# Power.net
KiCad netlist of a schematic drawn in Altium Designer
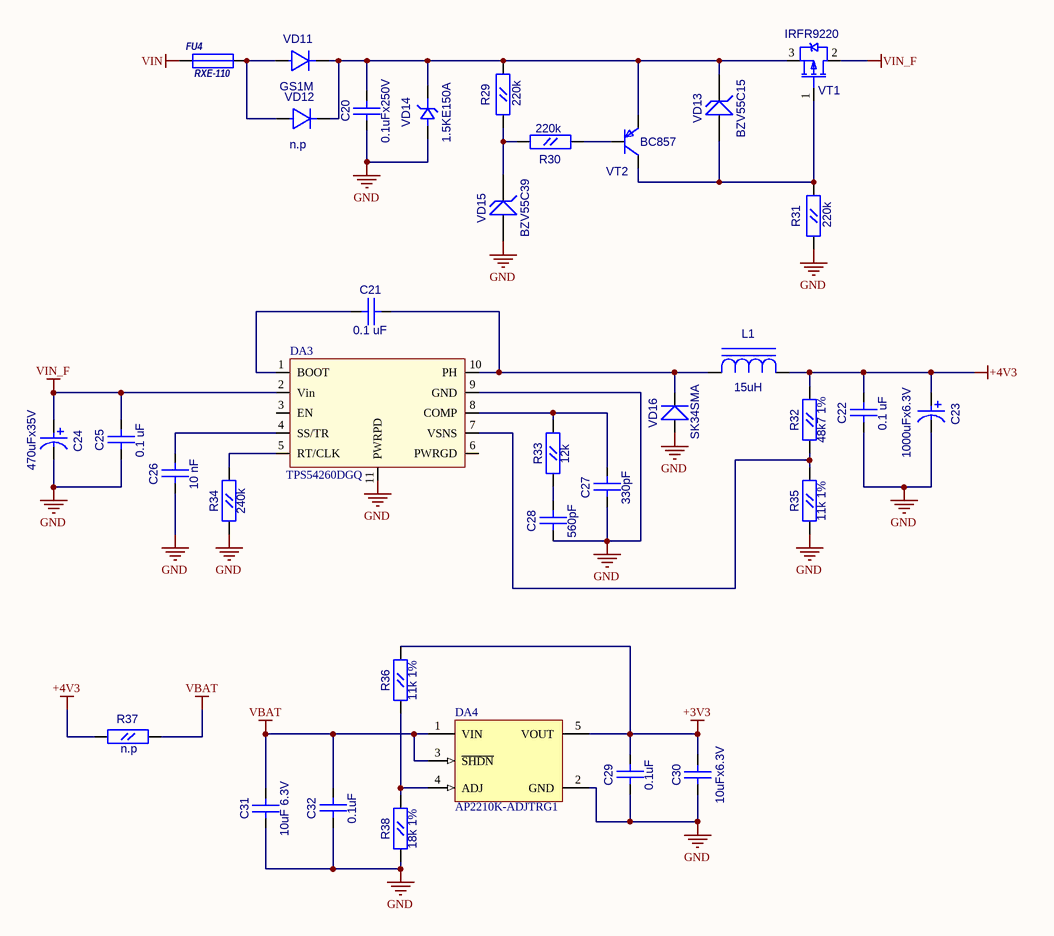
[diagram p0: Power.SchDoc]

(export (version "E")
  (design (tool "Eeschema 10.0.6"))
  (components
    (comp (ref "C20")
      (value "0.1uFx250V")
      (footprint "CC1206")
      (description "CC1206")
      (libsource (lib "gprs_modem_2") (part "CC1206"))
    )
    (comp (ref "C21")
      (value "0.1 uF")
      (footprint "CC0603")
      (description "CC0603")
      (libsource (lib "gprs_modem_2") (part "CC0603"))
    )
    (comp (ref "C22")
      (value "0.1 uF")
      (footprint "CC0603")
      (description "CC0603")
      (libsource (lib "gprs_modem_2") (part "CC0603"))
    )
    (comp (ref "C23")
      (value "1000uFx6.3V")
      (footprint "CC8X3.5")
      (description "CAP0.35")
      (libsource (lib "gprs_modem_2") (part "CAP0.35"))
    )
    (comp (ref "C24")
      (value "470uFx35V")
      (footprint "CC16X10_CAP0.5(1)(Primary)")
      (description "CAP0.5(1)")
      (libsource (lib "gprs_modem_2") (part "CAP0.5(1)"))
    )
    (comp (ref "C25")
      (value "0.1 uF")
      (footprint "CC0603")
      (description "CC0603")
      (libsource (lib "gprs_modem_2") (part "CC0603"))
    )
    (comp (ref "C26")
      (value "10 nF")
      (footprint "CC0603")
      (description "CC0603")
      (libsource (lib "gprs_modem_2") (part "CC0603"))
    )
    (comp (ref "C27")
      (value "330pF")
      (footprint "CC0603")
      (description "CC0603")
      (libsource (lib "gprs_modem_2") (part "CC0603"))
    )
    (comp (ref "C28")
      (value "560pF")
      (footprint "CC0603")
      (description "CC0603")
      (libsource (lib "gprs_modem_2") (part "CC0603"))
    )
    (comp (ref "C29")
      (value "0.1uF")
      (footprint "CC0603")
      (description "CC0603")
      (libsource (lib "gprs_modem_2") (part "CC0603"))
    )
    (comp (ref "C30")
      (value "10uFx6.3V")
      (footprint "CC0805")
      (description "CC0805")
      (libsource (lib "gprs_modem_2") (part "CC0805"))
    )
    (comp (ref "C31")
      (value "10uF 6.3V")
      (footprint "CC0805")
      (description "CC0805")
      (libsource (lib "gprs_modem_2") (part "CC0805"))
    )
    (comp (ref "C32")
      (value "0.1uF")
      (footprint "CC0603")
      (description "CC0603")
      (libsource (lib "gprs_modem_2") (part "CC0603"))
    )
    (comp (ref "DA3")
      (value "TPS54260DGQ")
      (footprint "S-PDSO-G10")
      (libsource (lib "gprs_modem_2") (part "TPS54260DGQ"))
    )
    (comp (ref "DA4")
      (value "AP2210K-ADJTRG1")
      (footprint "SOT23-5")
      (fields (field (name "PUBLISHER") "Altium Limited"))
      (libsource (lib "gprs_modem_2") (part "MCP1824T-ADJE/OT"))
    )
    (comp (ref "FU4")
      (value "RXE-110")
      (footprint "RXE-110")
      (libsource (lib "gprs_modem_2") (part "RXE-110"))
    )
    (comp (ref "L1")
      (value "15uH")
      (footprint "SDR0805")
      (description "SDR0805")
      (libsource (lib "gprs_modem_2") (part "SDR0805"))
    )
    (comp (ref "R29")
      (value "220k")
      (footprint "RC0603")
      (description "RC0603")
      (libsource (lib "gprs_modem_2") (part "RC0603"))
    )
    (comp (ref "R30")
      (value "220k")
      (footprint "RC0603")
      (description "RC0603")
      (libsource (lib "gprs_modem_2") (part "RC0603"))
    )
    (comp (ref "R31")
      (value "220k")
      (footprint "RC0603")
      (description "RC0603")
      (libsource (lib "gprs_modem_2") (part "RC0603"))
    )
    (comp (ref "R32")
      (value "48k7 1%")
      (footprint "RC0603")
      (description "RC0603")
      (libsource (lib "gprs_modem_2") (part "RC0603"))
    )
    (comp (ref "R33")
      (value "12k")
      (footprint "RC0603")
      (description "RC0603")
      (libsource (lib "gprs_modem_2") (part "RC0603"))
    )
    (comp (ref "R34")
      (value "240k")
      (footprint "RC0603")
      (description "RC0603")
      (libsource (lib "gprs_modem_2") (part "RC0603"))
    )
    (comp (ref "R35")
      (value "11k 1%")
      (footprint "RC0603")
      (description "RC0603")
      (libsource (lib "gprs_modem_2") (part "RC0603"))
    )
    (comp (ref "R36")
      (value "11k 1%")
      (footprint "RC0603")
      (description "RC0603")
      (libsource (lib "gprs_modem_2") (part "RC0603"))
    )
    (comp (ref "R37")
      (value "n.p")
      (footprint "RC0805")
      (description "RC0805")
      (libsource (lib "gprs_modem_2") (part "RC0805"))
    )
    (comp (ref "R38")
      (value "18k 1%")
      (footprint "RC0603")
      (description "RC0603")
      (libsource (lib "gprs_modem_2") (part "RC0603"))
    )
    (comp (ref "VD11") (value "GS1M") (footprint "SMA") (libsource (lib "gprs_modem_2") (part "GS1M")))
    (comp (ref "VD12")
      (value "n.p")
      (footprint "SMA")
      (description "GS1M")
      (libsource (lib "gprs_modem_2") (part "GS1M"))
    )
    (comp (ref "VD13")
      (value "BZV55C15")
      (footprint "SOD-80")
      (description "Zener Voltage Regulator Diode")
      (libsource (lib "gprs_modem_2") (part "BZV55C12"))
    )
    (comp (ref "VD14")
      (value "1.5KE150A")
      (footprint "DO-201")
      (description "1.5KE")
      (libsource (lib "gprs_modem_2") (part "1.5KE"))
    )
    (comp (ref "VD15")
      (value "BZV55C39")
      (footprint "SOD-80")
      (description "Zener Voltage Regulator Diode")
      (libsource (lib "gprs_modem_2") (part "BZV55C12"))
    )
    (comp (ref "VD16")
      (value "SK34SMA")
      (footprint "SMA")
      (description "Schottky Rectifier")
      (libsource (lib "gprs_modem") (part "SK34SMA"))
    )
    (comp (ref "VT1")
      (value "IRFR9220")
      (footprint "D-PAK(TO-252AA)")
      (description "HEXFET Power MOSFET")
      (libsource (lib "gprs_modem_2") (part "IRFR9220"))
    )
    (comp (ref "VT2")
      (value "BC857")
      (footprint "SOT-23(123)")
      (description "PNP 100ma transistor")
      (libsource (lib "gprs_modem_2") (part "BC857B"))
    )
  )
  (nets
    (net (code "1") (name "+3V3") (class "Default")
      (node (ref "C29") (pin "1") (pinfunction "A_1") (pintype "passive"))
      (node (ref "C30") (pin "2") (pinfunction "B_2") (pintype "passive"))
      (node (ref "DA4") (pin "5") (pinfunction "VOUT_5") (pintype "power_in"))
      (node (ref "R36") (pin "2") (pinfunction "B_2") (pintype "passive"))
    )
    (net (code "2") (name "+4V3") (class "Default")
      (node (ref "C22") (pin "1") (pinfunction "A_1") (pintype "passive"))
      (node (ref "C23") (pin "1") (pintype "passive"))
      (node (ref "L1") (pin "2") (pinfunction "A_2") (pintype "passive"))
      (node (ref "R32") (pin "2") (pinfunction "B_2") (pintype "passive"))
      (node (ref "R37") (pin "1") (pinfunction "A_1") (pintype "passive"))
    )
    (net (code "3") (name "GND") (class "Default")
      (node (ref "C20") (pin "1") (pinfunction "A_1") (pintype "passive"))
      (node (ref "C22") (pin "2") (pinfunction "B_2") (pintype "passive"))
      (node (ref "C23") (pin "2") (pintype "passive"))
      (node (ref "C24") (pin "1") (pintype "passive"))
      (node (ref "C25") (pin "2") (pinfunction "B_2") (pintype "passive"))
      (node (ref "C26") (pin "2") (pinfunction "B_2") (pintype "passive"))
      (node (ref "C27") (pin "2") (pinfunction "B_2") (pintype "passive"))
      (node (ref "C28") (pin "2") (pinfunction "B_2") (pintype "passive"))
      (node (ref "C29") (pin "2") (pinfunction "B_2") (pintype "passive"))
      (node (ref "C30") (pin "1") (pinfunction "A_1") (pintype "passive"))
      (node (ref "C31") (pin "1") (pinfunction "A_1") (pintype "passive"))
      (node (ref "C32") (pin "2") (pinfunction "B_2") (pintype "passive"))
      (node (ref "DA3") (pin "11") (pinfunction "PWRPD_11") (pintype "passive"))
      (node (ref "DA3") (pin "9") (pinfunction "GND_9") (pintype "passive"))
      (node (ref "DA4") (pin "2") (pinfunction "GND_2") (pintype "power_in"))
      (node (ref "R31") (pin "1") (pinfunction "A_1") (pintype "passive"))
      (node (ref "R34") (pin "1") (pinfunction "A_1") (pintype "passive"))
      (node (ref "R35") (pin "1") (pinfunction "A_1") (pintype "passive"))
      (node (ref "R38") (pin "1") (pinfunction "A_1") (pintype "passive"))
      (node (ref "VD14") (pin "1") (pinfunction "A_1") (pintype "passive"))
      (node (ref "VD15") (pin "1") (pinfunction "A_1") (pintype "passive"))
      (node (ref "VD16") (pin "1") (pinfunction "A_1") (pintype "passive"))
    )
    (net (code "4") (name "Net-(C20-B)") (class "Default")
      (node (ref "C20") (pin "2") (pinfunction "B_2") (pintype "passive"))
      (node (ref "R29") (pin "2") (pinfunction "B_2") (pintype "passive"))
      (node (ref "VD11") (pin "2") (pinfunction "K_2") (pintype "passive"))
      (node (ref "VD12") (pin "2") (pinfunction "K_2") (pintype "passive"))
      (node (ref "VD13") (pin "2") (pintype "passive"))
      (node (ref "VD14") (pin "2") (pinfunction "K_2") (pintype "passive"))
      (node (ref "VT1") (pin "3") (pinfunction "S_3") (pintype "passive"))
      (node (ref "VT2") (pin "2") (pinfunction "E_2") (pintype "passive"))
    )
    (net (code "5") (name "Net-(C21-A)") (class "Default")
      (node (ref "C21") (pin "1") (pinfunction "A_1") (pintype "passive"))
      (node (ref "DA3") (pin "10") (pinfunction "PH_10") (pintype "passive"))
      (node (ref "L1") (pin "1") (pinfunction "C_1") (pintype "passive"))
      (node (ref "VD16") (pin "2") (pinfunction "K_2") (pintype "passive"))
    )
    (net (code "6") (name "Net-(C21-B)") (class "Default")
      (node (ref "C21") (pin "2") (pinfunction "B_2") (pintype "passive"))
      (node (ref "DA3") (pin "1") (pinfunction "BOOT_1") (pintype "passive"))
    )
    (net (code "7") (name "Net-(C26-A)") (class "Default")
      (node (ref "C26") (pin "1") (pinfunction "A_1") (pintype "passive"))
      (node (ref "DA3") (pin "4") (pinfunction "SS/TR_4") (pintype "passive"))
    )
    (net (code "8") (name "Net-(C27-A)") (class "Default")
      (node (ref "C27") (pin "1") (pinfunction "A_1") (pintype "passive"))
      (node (ref "DA3") (pin "8") (pinfunction "COMP_8") (pintype "passive"))
      (node (ref "R33") (pin "2") (pinfunction "B_2") (pintype "passive"))
    )
    (net (code "9") (name "Net-(C28-A)") (class "Default")
      (node (ref "C28") (pin "1") (pinfunction "A_1") (pintype "passive"))
      (node (ref "R33") (pin "1") (pinfunction "A_1") (pintype "passive"))
    )
    (net (code "10") (name "Net-(DA3-RT{slash}CLK)") (class "Default")
      (node (ref "DA3") (pin "5") (pinfunction "RT/CLK_5") (pintype "passive"))
      (node (ref "R34") (pin "2") (pinfunction "B_2") (pintype "passive"))
    )
    (net (code "11") (name "Net-(DA3-VSNS)") (class "Default")
      (node (ref "DA3") (pin "7") (pinfunction "VSNS_7") (pintype "passive"))
      (node (ref "R32") (pin "1") (pinfunction "A_1") (pintype "passive"))
      (node (ref "R35") (pin "2") (pinfunction "B_2") (pintype "passive"))
    )
    (net (code "12") (name "Net-(DA4-ADJ)") (class "Default")
      (node (ref "DA4") (pin "4") (pinfunction "ADJ_4") (pintype "input"))
      (node (ref "R36") (pin "1") (pinfunction "A_1") (pintype "passive"))
      (node (ref "R38") (pin "2") (pinfunction "B_2") (pintype "passive"))
    )
    (net (code "13") (name "Net-(R29-A)") (class "Default")
      (node (ref "R29") (pin "1") (pinfunction "A_1") (pintype "passive"))
      (node (ref "R30") (pin "2") (pinfunction "B_2") (pintype "passive"))
      (node (ref "VD15") (pin "2") (pintype "passive"))
    )
    (net (code "14") (name "Net-(R30-A)") (class "Default")
      (node (ref "R30") (pin "1") (pinfunction "A_1") (pintype "passive"))
      (node (ref "VT2") (pin "1") (pinfunction "B_1") (pintype "passive"))
    )
    (net (code "15") (name "Net-(R31-B)") (class "Default")
      (node (ref "R31") (pin "2") (pinfunction "B_2") (pintype "passive"))
      (node (ref "VD13") (pin "1") (pinfunction "A_1") (pintype "passive"))
      (node (ref "VT1") (pin "1") (pinfunction "G_1") (pintype "passive"))
      (node (ref "VT2") (pin "3") (pinfunction "C_3") (pintype "passive"))
    )
    (net (code "16") (name "Net-(VD11-A)") (class "Default")
      (node (ref "FU4") (pin "2") (pintype "passive"))
      (node (ref "VD11") (pin "1") (pinfunction "A_1") (pintype "passive"))
      (node (ref "VD12") (pin "1") (pinfunction "A_1") (pintype "passive"))
    )
    (net (code "17") (name "VBAT") (class "Default")
      (node (ref "C31") (pin "2") (pinfunction "B_2") (pintype "passive"))
      (node (ref "C32") (pin "1") (pinfunction "A_1") (pintype "passive"))
      (node (ref "DA4") (pin "1") (pinfunction "VIN_1") (pintype "power_in"))
      (node (ref "DA4") (pin "3") (pinfunction "~{SHDN}_3") (pintype "input"))
      (node (ref "R37") (pin "2") (pinfunction "B_2") (pintype "passive"))
    )
    (net (code "18") (name "VIN") (class "Default") (node (ref "FU4") (pin "1") (pintype "passive")))
    (net (code "19") (name "VIN_F") (class "Default")
      (node (ref "C24") (pin "2") (pintype "passive"))
      (node (ref "C25") (pin "1") (pinfunction "A_1") (pintype "passive"))
      (node (ref "DA3") (pin "2") (pinfunction "Vin_2") (pintype "passive"))
      (node (ref "VT1") (pin "2") (pinfunction "D_2") (pintype "passive"))
    )
    (net (code "20") (name "unconnected-(DA3-EN-Pad3)") (class "Default")
      (node (ref "DA3") (pin "3") (pinfunction "EN_3") (pintype "passive"))
    )
    (net (code "21") (name "unconnected-(DA3-PWRGD-Pad6)") (class "Default")
      (node (ref "DA3") (pin "6") (pinfunction "PWRGD_6") (pintype "passive"))
    )
  )
)
